# RFM95_LoRa_Breakout_Board_2021-05-26.net
KiCad netlist of a schematic drawn in EasyEDA
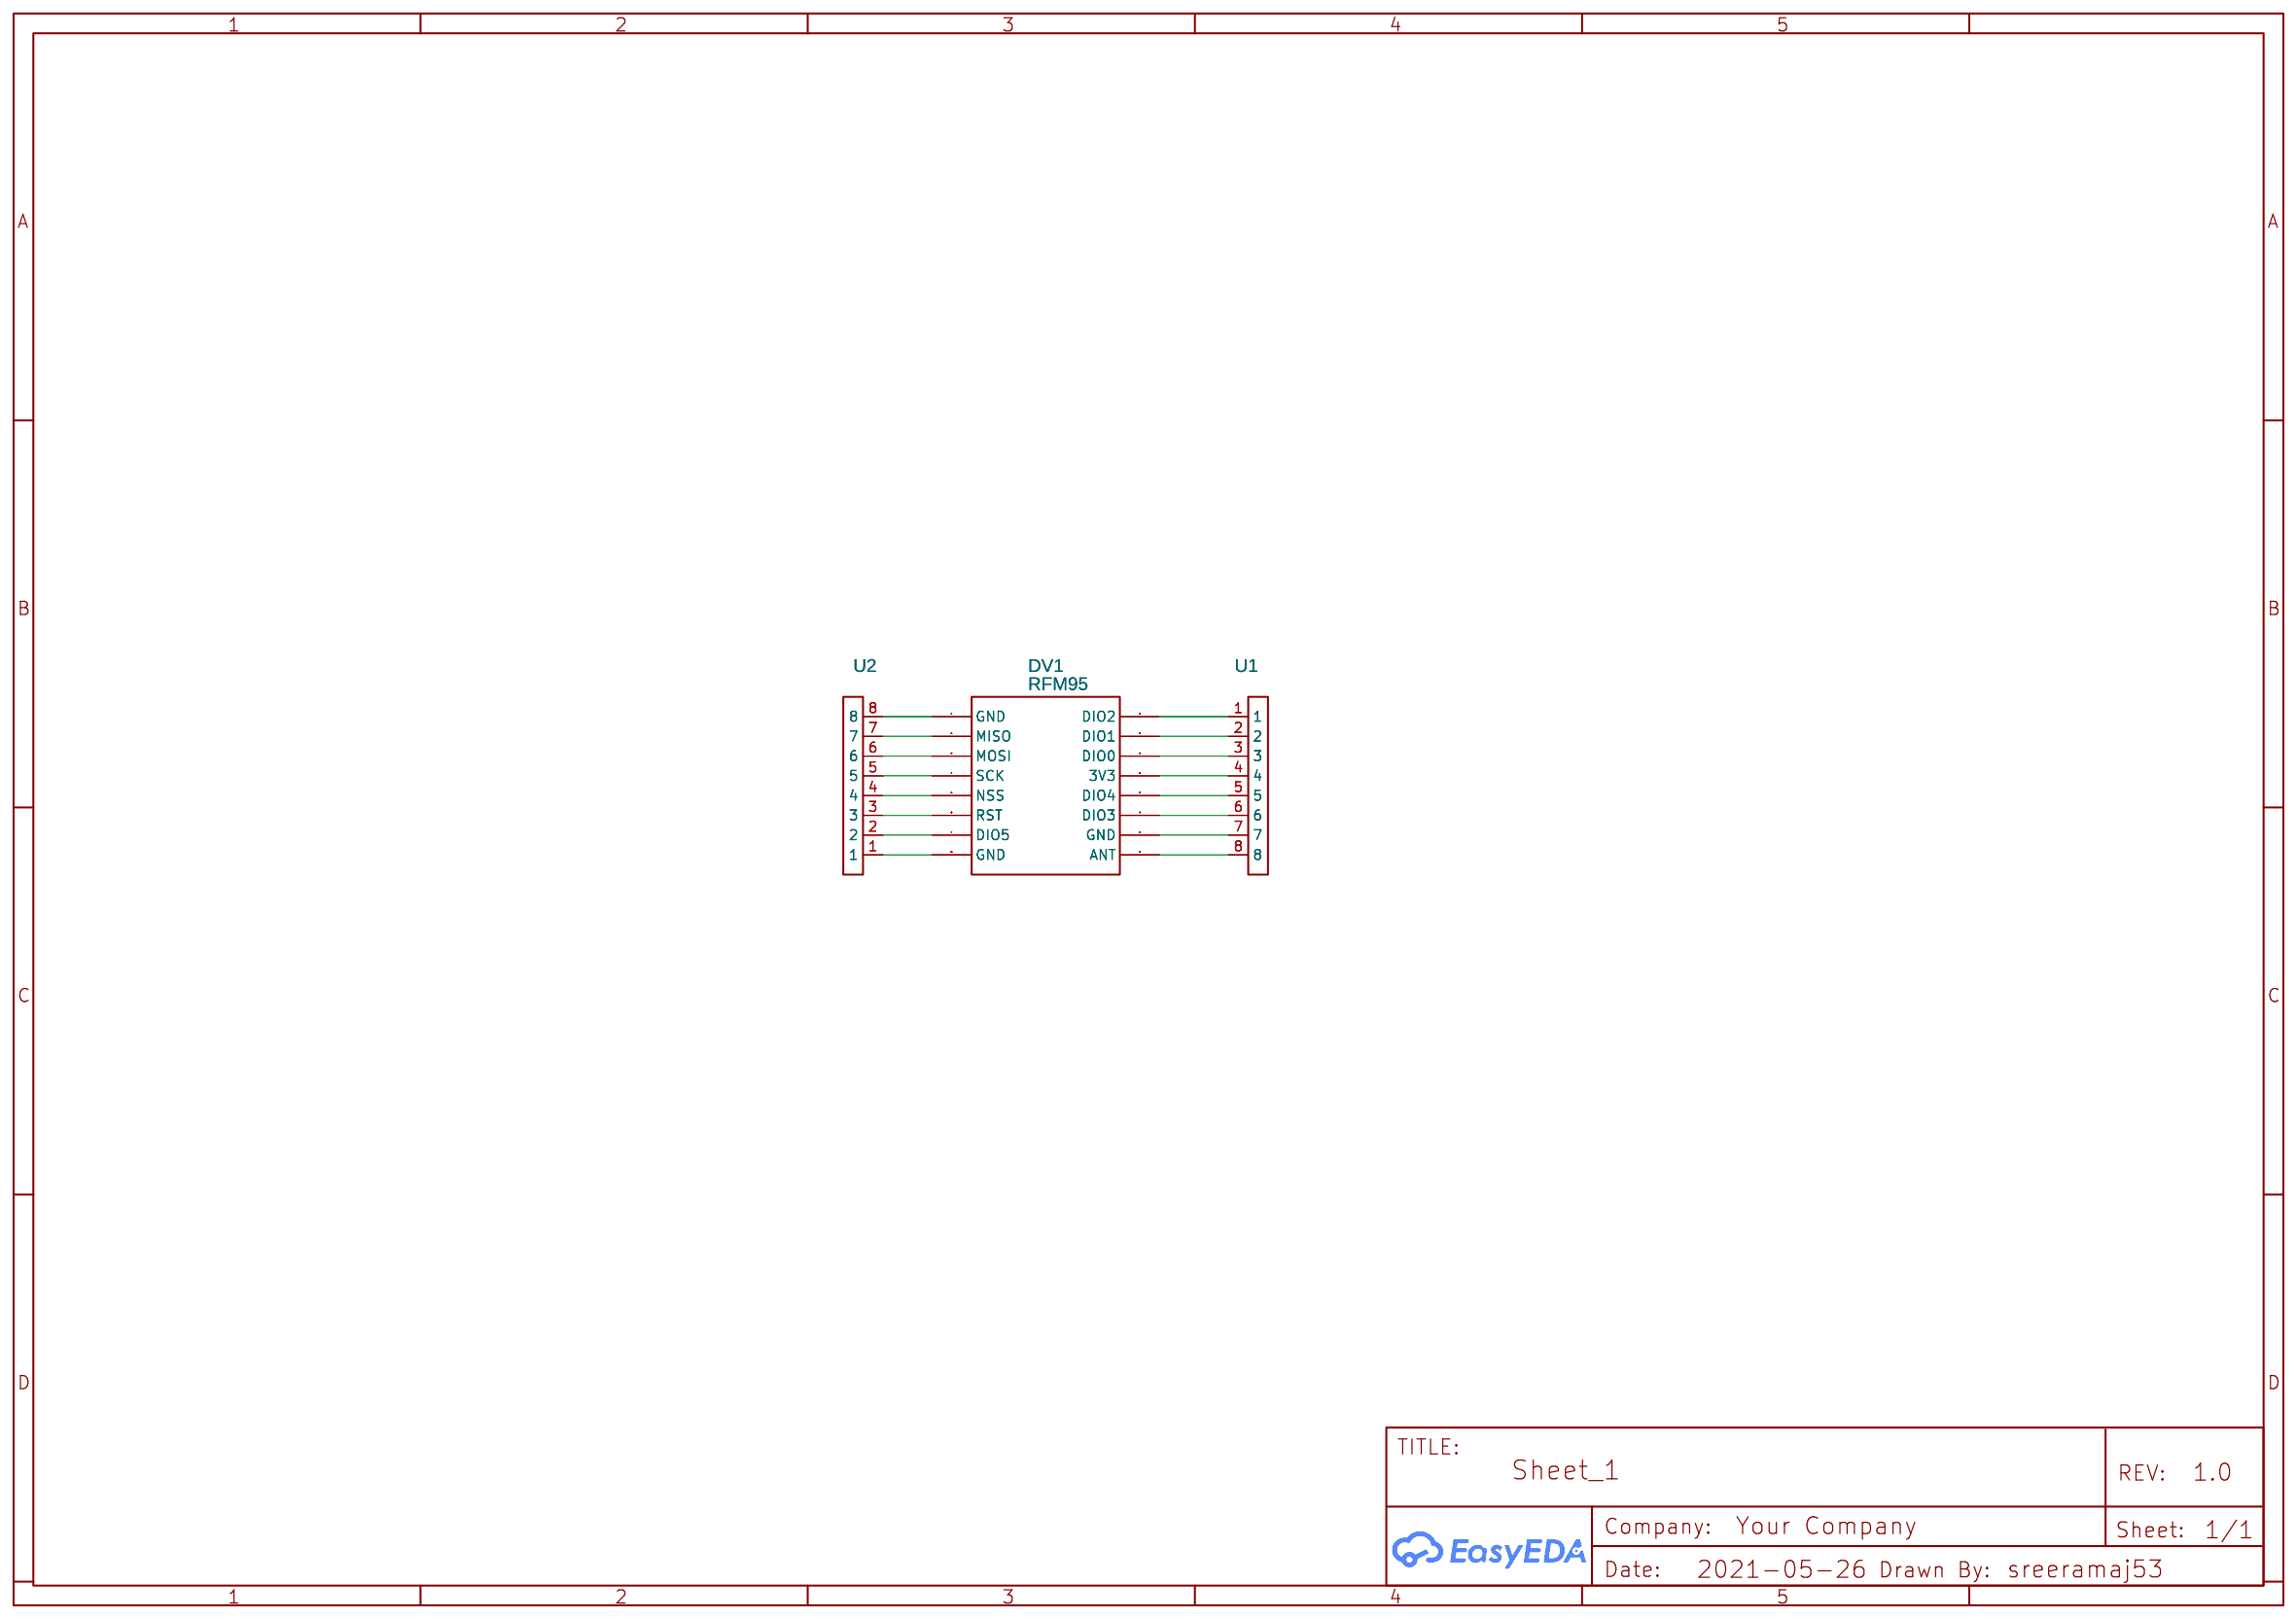
[diagram p0: schematic sheet]

(export (version "E")
  (design (tool "Eeschema 10.0.6"))
  (components
    (comp (ref "DV1") (value "RFM95") (libsource (lib "") (part "RFM95")))
    (comp (ref "U1") (value "8 PIN HEADER") (libsource (lib "") (part "8 PIN HEADER")))
    (comp (ref "U2") (value "8 PIN HEADER") (libsource (lib "") (part "8 PIN HEADER_1")))
  )
  (nets
    (net (code "1") (name "Net-(DV1-3V3)") (class "Default")
      (node (ref "DV1") (pin "13") (pinfunction "3V3_13") (pintype "bidirectional"))
      (node (ref "U1") (pin "4") (pinfunction "4_4") (pintype "unspecified"))
    )
    (net (code "2") (name "Net-(DV1-ANT)") (class "Default")
      (node (ref "DV1") (pin "9") (pinfunction "ANT_9") (pintype "bidirectional"))
      (node (ref "U1") (pin "8") (pinfunction "8_8") (pintype "unspecified"))
    )
    (net (code "3") (name "Net-(DV1-DIO0)") (class "Default")
      (node (ref "DV1") (pin "14") (pinfunction "DIO0_14") (pintype "bidirectional"))
      (node (ref "U1") (pin "3") (pinfunction "3_3") (pintype "unspecified"))
    )
    (net (code "4") (name "Net-(DV1-DIO1)") (class "Default")
      (node (ref "DV1") (pin "15") (pinfunction "DIO1_15") (pintype "bidirectional"))
      (node (ref "U1") (pin "2") (pinfunction "2_2") (pintype "unspecified"))
    )
    (net (code "5") (name "Net-(DV1-DIO2)") (class "Default")
      (node (ref "DV1") (pin "16") (pinfunction "DIO2_16") (pintype "bidirectional"))
      (node (ref "U1") (pin "1") (pinfunction "1_1") (pintype "unspecified"))
    )
    (net (code "6") (name "Net-(DV1-DIO3)") (class "Default")
      (node (ref "DV1") (pin "11") (pinfunction "DIO3_11") (pintype "bidirectional"))
      (node (ref "U1") (pin "6") (pinfunction "6_6") (pintype "unspecified"))
    )
    (net (code "7") (name "Net-(DV1-DIO4)") (class "Default")
      (node (ref "DV1") (pin "12") (pinfunction "DIO4_12") (pintype "bidirectional"))
      (node (ref "U1") (pin "5") (pinfunction "5_5") (pintype "unspecified"))
    )
    (net (code "8") (name "Net-(DV1-DIO5)") (class "Default")
      (node (ref "DV1") (pin "7") (pinfunction "DIO5_7") (pintype "bidirectional"))
      (node (ref "U2") (pin "2") (pinfunction "2_2") (pintype "unspecified"))
    )
    (net (code "9") (name "Net-(DV1-GND-Pad1)") (class "Default")
      (node (ref "DV1") (pin "1") (pinfunction "GND_1") (pintype "bidirectional"))
      (node (ref "U2") (pin "8") (pinfunction "8_8") (pintype "unspecified"))
    )
    (net (code "10") (name "Net-(DV1-GND-Pad8)") (class "Default")
      (node (ref "DV1") (pin "8") (pinfunction "GND_8") (pintype "bidirectional"))
      (node (ref "U2") (pin "1") (pinfunction "1_1") (pintype "unspecified"))
    )
    (net (code "11") (name "Net-(DV1-GND-Pad10)") (class "Default")
      (node (ref "DV1") (pin "10") (pinfunction "GND_10") (pintype "bidirectional"))
      (node (ref "U1") (pin "7") (pinfunction "7_7") (pintype "unspecified"))
    )
    (net (code "12") (name "Net-(DV1-MISO)") (class "Default")
      (node (ref "DV1") (pin "2") (pinfunction "MISO_2") (pintype "bidirectional"))
      (node (ref "U2") (pin "7") (pinfunction "7_7") (pintype "unspecified"))
    )
    (net (code "13") (name "Net-(DV1-MOSI)") (class "Default")
      (node (ref "DV1") (pin "3") (pinfunction "MOSI_3") (pintype "bidirectional"))
      (node (ref "U2") (pin "6") (pinfunction "6_6") (pintype "unspecified"))
    )
    (net (code "14") (name "Net-(DV1-NSS)") (class "Default")
      (node (ref "DV1") (pin "5") (pinfunction "NSS_5") (pintype "bidirectional"))
      (node (ref "U2") (pin "4") (pinfunction "4_4") (pintype "unspecified"))
    )
    (net (code "15") (name "Net-(DV1-RST)") (class "Default")
      (node (ref "DV1") (pin "6") (pinfunction "RST_6") (pintype "bidirectional"))
      (node (ref "U2") (pin "3") (pinfunction "3_3") (pintype "unspecified"))
    )
    (net (code "16") (name "Net-(DV1-SCK)") (class "Default")
      (node (ref "DV1") (pin "4") (pinfunction "SCK_4") (pintype "bidirectional"))
      (node (ref "U2") (pin "5") (pinfunction "5_5") (pintype "unspecified"))
    )
  )
)
